# wd-adapter.net
KiCad netlist of a schematic drawn in EAGLE
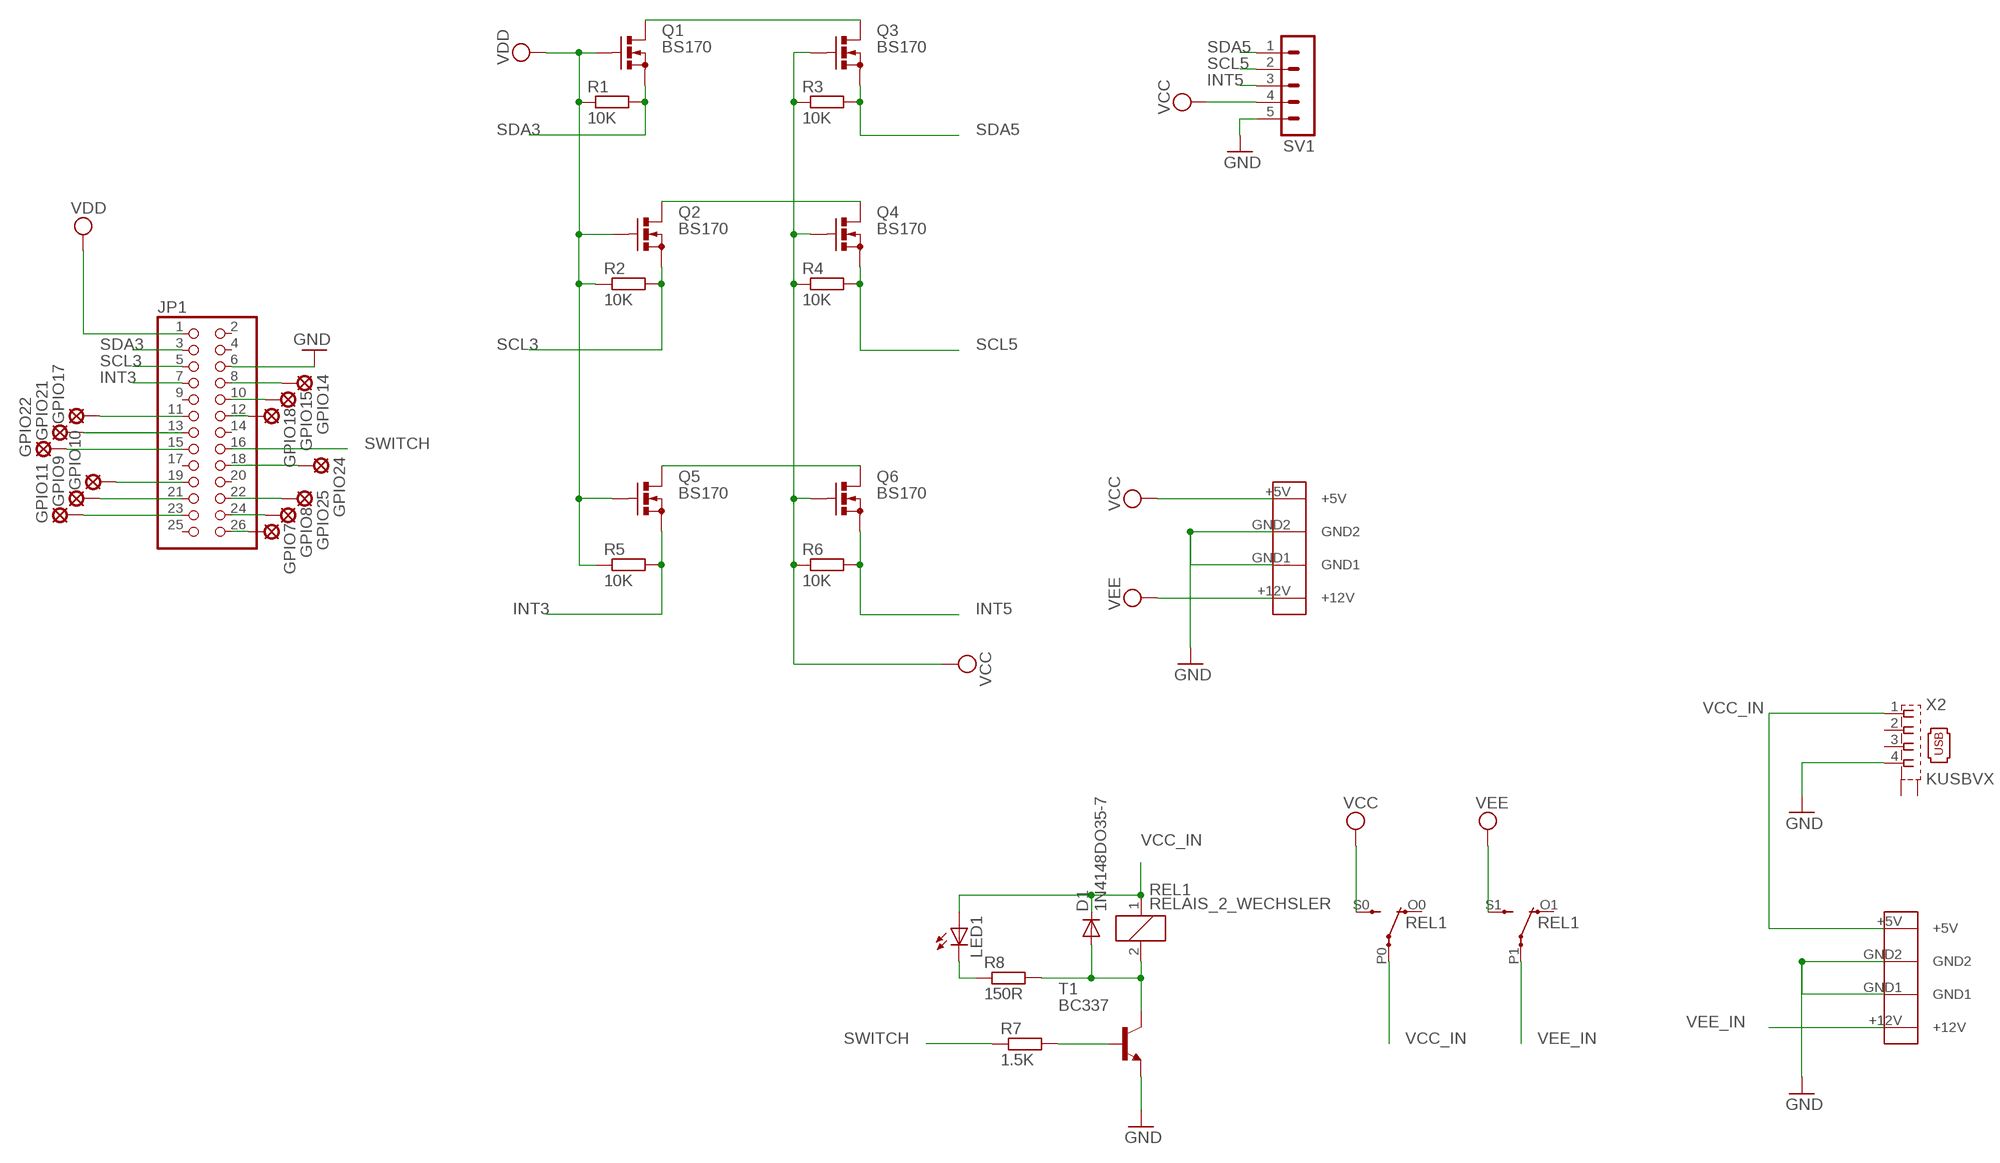
[diagram p0: schematic, sheet 1]

(export (version "E")
  (design (tool "Eeschema 10.0.6"))
  (components
    (comp (ref "D1")
      (value "1N4148DO35-7")
      (footprint "eagle-import:DO35-7")
      (libsource (lib "eagle-import") (part "1N4148DO35-7"))
    )
    (comp (ref "GPIO7")
      (value "LSP10")
      (footprint "eagle-import:LSP10")
      (libsource (lib "eagle-import") (part "LSP10"))
    )
    (comp (ref "GPIO8")
      (value "LSP10")
      (footprint "eagle-import:LSP10")
      (libsource (lib "eagle-import") (part "LSP10"))
    )
    (comp (ref "GPIO9")
      (value "LSP10")
      (footprint "eagle-import:LSP10")
      (libsource (lib "eagle-import") (part "LSP10"))
    )
    (comp (ref "GPIO10")
      (value "LSP10")
      (footprint "eagle-import:LSP10")
      (libsource (lib "eagle-import") (part "LSP10"))
    )
    (comp (ref "GPIO11")
      (value "LSP10")
      (footprint "eagle-import:LSP10")
      (libsource (lib "eagle-import") (part "LSP10"))
    )
    (comp (ref "GPIO14")
      (value "LSP10")
      (footprint "eagle-import:LSP10")
      (libsource (lib "eagle-import") (part "LSP10"))
    )
    (comp (ref "GPIO15")
      (value "LSP10")
      (footprint "eagle-import:LSP10")
      (libsource (lib "eagle-import") (part "LSP10"))
    )
    (comp (ref "GPIO17")
      (value "GPIO17")
      (footprint "eagle-import:LSP10")
      (libsource (lib "eagle-import") (part "LSP10"))
    )
    (comp (ref "GPIO18")
      (value "LSP10")
      (footprint "eagle-import:LSP10")
      (libsource (lib "eagle-import") (part "LSP10"))
    )
    (comp (ref "GPIO21")
      (value "LSP10")
      (footprint "eagle-import:LSP10")
      (libsource (lib "eagle-import") (part "LSP10"))
    )
    (comp (ref "GPIO22")
      (value "LSP10")
      (footprint "eagle-import:LSP10")
      (libsource (lib "eagle-import") (part "LSP10"))
    )
    (comp (ref "GPIO24")
      (value "LSP10")
      (footprint "eagle-import:LSP10")
      (libsource (lib "eagle-import") (part "LSP10"))
    )
    (comp (ref "GPIO25")
      (value "LSP10")
      (footprint "eagle-import:LSP10")
      (libsource (lib "eagle-import") (part "LSP10"))
    )
    (comp (ref "JP1")
      (value "PINHD-2X13")
      (footprint "eagle-import:2X13")
      (libsource (lib "eagle-import") (part "PINHD-2X13"))
    )
    (comp (ref "LED1")
      (value "LED3MM")
      (footprint "eagle-import:LED3MM")
      (libsource (lib "eagle-import") (part "LED3MM"))
    )
    (comp (ref "Q1")
      (value "BS170")
      (footprint "eagle-import:SOT54E")
      (libsource (lib "eagle-import") (part "BS170"))
    )
    (comp (ref "Q2")
      (value "BS170")
      (footprint "eagle-import:SOT54E")
      (libsource (lib "eagle-import") (part "BS170"))
    )
    (comp (ref "Q3")
      (value "BS170")
      (footprint "eagle-import:SOT54E")
      (libsource (lib "eagle-import") (part "BS170"))
    )
    (comp (ref "Q4")
      (value "BS170")
      (footprint "eagle-import:SOT54E")
      (libsource (lib "eagle-import") (part "BS170"))
    )
    (comp (ref "Q5")
      (value "BS170")
      (footprint "eagle-import:SOT54E")
      (libsource (lib "eagle-import") (part "BS170"))
    )
    (comp (ref "Q6")
      (value "BS170")
      (footprint "eagle-import:SOT54E")
      (libsource (lib "eagle-import") (part "BS170"))
    )
    (comp (ref "R1")
      (value "10K")
      (footprint "eagle-import:0207_2V")
      (libsource (lib "eagle-import") (part "R-EU_0207/2V"))
    )
    (comp (ref "R2")
      (value "10K")
      (footprint "eagle-import:0207_2V")
      (libsource (lib "eagle-import") (part "R-EU_0207/2V"))
    )
    (comp (ref "R3")
      (value "10K")
      (footprint "eagle-import:0207_2V")
      (libsource (lib "eagle-import") (part "R-EU_0207/2V"))
    )
    (comp (ref "R4")
      (value "10K")
      (footprint "eagle-import:0207_2V")
      (libsource (lib "eagle-import") (part "R-EU_0207/2V"))
    )
    (comp (ref "R5")
      (value "10K")
      (footprint "eagle-import:0207_2V")
      (libsource (lib "eagle-import") (part "R-EU_0207/2V"))
    )
    (comp (ref "R6")
      (value "10K")
      (footprint "eagle-import:0207_2V")
      (libsource (lib "eagle-import") (part "R-EU_0207/2V"))
    )
    (comp (ref "R7")
      (value "1.5K")
      (footprint "eagle-import:0207_7")
      (libsource (lib "eagle-import") (part "R-EU_0207/7"))
    )
    (comp (ref "R8")
      (value "150R")
      (footprint "eagle-import:0207_2V")
      (libsource (lib "eagle-import") (part "R-EU_0207/2V"))
    )
    (comp (ref "REL1")
      (value "RELAIS_2_WECHSLER")
      (footprint "eagle-import:RELAIS_DIL_M4")
      (libsource (lib "eagle-import") (part "RELAIS_2_WECHSLER"))
    )
    (comp (ref "SV1")
      (value "MA05-1")
      (footprint "eagle-import:MA05-1")
      (libsource (lib "eagle-import") (part "MA05-1"))
    )
    (comp (ref "T1")
      (value "BC337")
      (footprint "eagle-import:TO92")
      (libsource (lib "eagle-import") (part "BC337"))
    )
    (comp (ref "U$1")
      (value "PSW_5")
      (footprint "eagle-import:PSW_5")
      (libsource (lib "eagle-import") (part "PSW_5"))
    )
    (comp (ref "U$3")
      (value "PSW_5")
      (footprint "eagle-import:PSW_5")
      (libsource (lib "eagle-import") (part "PSW_5"))
    )
    (comp (ref "X2")
      (value "KUSBVX")
      (footprint "eagle-import:KUSBVX")
      (libsource (lib "eagle-import") (part "KUSBVX"))
    )
  )
  (nets
    (net (code "1") (name "/INT3") (class "Default")
      (node (ref "JP1") (pin "7") (pinfunction "7_7") (pintype "passive"))
      (node (ref "Q5") (pin "S") (pinfunction "S_S") (pintype "passive"))
      (node (ref "R5") (pin "2") (pinfunction "2_2") (pintype "passive"))
    )
    (net (code "2") (name "/INT5") (class "Default")
      (node (ref "Q6") (pin "S") (pinfunction "S_S") (pintype "passive"))
      (node (ref "R6") (pin "2") (pinfunction "2_2") (pintype "passive"))
      (node (ref "SV1") (pin "3") (pinfunction "3_3") (pintype "passive"))
    )
    (net (code "3") (name "/SCL3") (class "Default")
      (node (ref "JP1") (pin "5") (pinfunction "5_5") (pintype "passive"))
      (node (ref "Q2") (pin "S") (pinfunction "S_S") (pintype "passive"))
      (node (ref "R2") (pin "2") (pinfunction "2_2") (pintype "passive"))
    )
    (net (code "4") (name "/SCL5") (class "Default")
      (node (ref "Q4") (pin "S") (pinfunction "S_S") (pintype "passive"))
      (node (ref "R4") (pin "2") (pinfunction "2_2") (pintype "passive"))
      (node (ref "SV1") (pin "2") (pinfunction "2_2") (pintype "passive"))
    )
    (net (code "5") (name "/SDA3") (class "Default")
      (node (ref "JP1") (pin "3") (pinfunction "3_3") (pintype "passive"))
      (node (ref "Q1") (pin "S") (pinfunction "S_S") (pintype "passive"))
      (node (ref "R1") (pin "2") (pinfunction "2_2") (pintype "passive"))
    )
    (net (code "6") (name "/SDA5") (class "Default")
      (node (ref "Q3") (pin "S") (pinfunction "S_S") (pintype "passive"))
      (node (ref "R3") (pin "2") (pinfunction "2_2") (pintype "passive"))
      (node (ref "SV1") (pin "1") (pinfunction "1_1") (pintype "passive"))
    )
    (net (code "7") (name "/SWITCH") (class "Default")
      (node (ref "JP1") (pin "16") (pinfunction "16_16") (pintype "passive"))
      (node (ref "R7") (pin "1") (pinfunction "1_1") (pintype "passive"))
    )
    (net (code "8") (name "/VCC_IN") (class "Default")
      (node (ref "D1") (pin "C") (pinfunction "C_C") (pintype "passive"))
      (node (ref "LED1") (pin "A") (pinfunction "A_A") (pintype "passive"))
      (node (ref "REL1") (pin "1") (pinfunction "1_1") (pintype "passive"))
      (node (ref "REL1") (pin "P0") (pinfunction "P_P0") (pintype "passive"))
      (node (ref "U$3") (pin "+5V") (pinfunction "+5V_+5V") (pintype "bidirectional"))
      (node (ref "X2") (pin "1") (pinfunction "1_1") (pintype "passive"))
    )
    (net (code "9") (name "/VEE_IN") (class "Default")
      (node (ref "REL1") (pin "P1") (pinfunction "P_P1") (pintype "passive"))
      (node (ref "U$3") (pin "+12V") (pinfunction "+12V_+12V") (pintype "bidirectional"))
    )
    (net (code "10") (name "GND") (class "Default")
      (node (ref "JP1") (pin "6") (pinfunction "6_6") (pintype "passive"))
      (node (ref "SV1") (pin "5") (pinfunction "5_5") (pintype "passive"))
      (node (ref "T1") (pin "1") (pinfunction "E_1") (pintype "passive"))
      (node (ref "U$1") (pin "GND1") (pinfunction "GND1_GND1") (pintype "bidirectional"))
      (node (ref "U$1") (pin "GND2") (pinfunction "GND2_GND2") (pintype "bidirectional"))
      (node (ref "U$3") (pin "GND1") (pinfunction "GND1_GND1") (pintype "bidirectional"))
      (node (ref "U$3") (pin "GND2") (pinfunction "GND2_GND2") (pintype "bidirectional"))
      (node (ref "X2") (pin "4") (pinfunction "4_4") (pintype "passive"))
    )
    (net (code "11") (name "Net-(GPIO7-PadMP)") (class "Default")
      (node (ref "GPIO7") (pin "MP") (pinfunction "MP_MP") (pintype "passive"))
      (node (ref "JP1") (pin "26") (pinfunction "26_26") (pintype "passive"))
    )
    (net (code "12") (name "Net-(GPIO8-PadMP)") (class "Default")
      (node (ref "GPIO8") (pin "MP") (pinfunction "MP_MP") (pintype "passive"))
      (node (ref "JP1") (pin "24") (pinfunction "24_24") (pintype "passive"))
    )
    (net (code "13") (name "Net-(GPIO9-PadMP)") (class "Default")
      (node (ref "GPIO9") (pin "MP") (pinfunction "MP_MP") (pintype "passive"))
      (node (ref "JP1") (pin "21") (pinfunction "21_21") (pintype "passive"))
    )
    (net (code "14") (name "Net-(GPIO10-PadMP)") (class "Default")
      (node (ref "GPIO10") (pin "MP") (pinfunction "MP_MP") (pintype "passive"))
      (node (ref "JP1") (pin "19") (pinfunction "19_19") (pintype "passive"))
    )
    (net (code "15") (name "Net-(GPIO11-PadMP)") (class "Default")
      (node (ref "GPIO11") (pin "MP") (pinfunction "MP_MP") (pintype "passive"))
      (node (ref "JP1") (pin "23") (pinfunction "23_23") (pintype "passive"))
    )
    (net (code "16") (name "Net-(GPIO14-PadMP)") (class "Default")
      (node (ref "GPIO14") (pin "MP") (pinfunction "MP_MP") (pintype "passive"))
      (node (ref "JP1") (pin "8") (pinfunction "8_8") (pintype "passive"))
    )
    (net (code "17") (name "Net-(GPIO15-PadMP)") (class "Default")
      (node (ref "GPIO15") (pin "MP") (pinfunction "MP_MP") (pintype "passive"))
      (node (ref "JP1") (pin "10") (pinfunction "10_10") (pintype "passive"))
    )
    (net (code "18") (name "Net-(GPIO17-PadMP)") (class "Default")
      (node (ref "GPIO17") (pin "MP") (pinfunction "MP_MP") (pintype "passive"))
      (node (ref "JP1") (pin "11") (pinfunction "11_11") (pintype "passive"))
    )
    (net (code "19") (name "Net-(GPIO18-PadMP)") (class "Default")
      (node (ref "GPIO18") (pin "MP") (pinfunction "MP_MP") (pintype "passive"))
      (node (ref "JP1") (pin "12") (pinfunction "12_12") (pintype "passive"))
    )
    (net (code "20") (name "Net-(GPIO21-PadMP)") (class "Default")
      (node (ref "GPIO21") (pin "MP") (pinfunction "MP_MP") (pintype "passive"))
      (node (ref "JP1") (pin "13") (pinfunction "13_13") (pintype "passive"))
    )
    (net (code "21") (name "Net-(GPIO22-PadMP)") (class "Default")
      (node (ref "GPIO22") (pin "MP") (pinfunction "MP_MP") (pintype "passive"))
      (node (ref "JP1") (pin "15") (pinfunction "15_15") (pintype "passive"))
    )
    (net (code "22") (name "Net-(GPIO24-PadMP)") (class "Default")
      (node (ref "GPIO24") (pin "MP") (pinfunction "MP_MP") (pintype "passive"))
      (node (ref "JP1") (pin "18") (pinfunction "18_18") (pintype "passive"))
    )
    (net (code "23") (name "Net-(GPIO25-PadMP)") (class "Default")
      (node (ref "GPIO25") (pin "MP") (pinfunction "MP_MP") (pintype "passive"))
      (node (ref "JP1") (pin "22") (pinfunction "22_22") (pintype "passive"))
    )
    (net (code "24") (name "Net-(LED1-C)") (class "Default")
      (node (ref "LED1") (pin "K") (pinfunction "C_K") (pintype "passive"))
      (node (ref "R8") (pin "1") (pinfunction "1_1") (pintype "passive"))
    )
    (net (code "25") (name "Net-(Q1-PadD)") (class "Default")
      (node (ref "Q1") (pin "D") (pinfunction "D_D") (pintype "passive"))
      (node (ref "Q3") (pin "D") (pinfunction "D_D") (pintype "passive"))
    )
    (net (code "26") (name "Net-(Q2-PadD)") (class "Default")
      (node (ref "Q2") (pin "D") (pinfunction "D_D") (pintype "passive"))
      (node (ref "Q4") (pin "D") (pinfunction "D_D") (pintype "passive"))
    )
    (net (code "27") (name "Net-(Q5-PadD)") (class "Default")
      (node (ref "Q5") (pin "D") (pinfunction "D_D") (pintype "passive"))
      (node (ref "Q6") (pin "D") (pinfunction "D_D") (pintype "passive"))
    )
    (net (code "28") (name "Net-(T1-B)") (class "Default")
      (node (ref "R7") (pin "2") (pinfunction "2_2") (pintype "passive"))
      (node (ref "T1") (pin "2") (pinfunction "B_2") (pintype "passive"))
    )
    (net (code "29") (name "Net-(T1-C)") (class "Default")
      (node (ref "D1") (pin "A") (pinfunction "A_A") (pintype "passive"))
      (node (ref "R8") (pin "2") (pinfunction "2_2") (pintype "passive"))
      (node (ref "REL1") (pin "2") (pinfunction "2_2") (pintype "passive"))
      (node (ref "T1") (pin "3") (pinfunction "C_3") (pintype "passive"))
    )
    (net (code "30") (name "VCC") (class "Default")
      (node (ref "Q3") (pin "G") (pinfunction "G_G") (pintype "passive"))
      (node (ref "Q4") (pin "G") (pinfunction "G_G") (pintype "passive"))
      (node (ref "Q6") (pin "G") (pinfunction "G_G") (pintype "passive"))
      (node (ref "R3") (pin "1") (pinfunction "1_1") (pintype "passive"))
      (node (ref "R4") (pin "1") (pinfunction "1_1") (pintype "passive"))
      (node (ref "R6") (pin "1") (pinfunction "1_1") (pintype "passive"))
      (node (ref "REL1") (pin "S0") (pinfunction "S_S0") (pintype "passive"))
      (node (ref "SV1") (pin "4") (pinfunction "4_4") (pintype "passive"))
      (node (ref "U$1") (pin "+5V") (pinfunction "+5V_+5V") (pintype "bidirectional"))
    )
    (net (code "31") (name "VDD") (class "Default")
      (node (ref "JP1") (pin "1") (pinfunction "1_1") (pintype "passive"))
      (node (ref "Q1") (pin "G") (pinfunction "G_G") (pintype "passive"))
      (node (ref "Q2") (pin "G") (pinfunction "G_G") (pintype "passive"))
      (node (ref "Q5") (pin "G") (pinfunction "G_G") (pintype "passive"))
      (node (ref "R1") (pin "1") (pinfunction "1_1") (pintype "passive"))
      (node (ref "R2") (pin "1") (pinfunction "1_1") (pintype "passive"))
      (node (ref "R5") (pin "1") (pinfunction "1_1") (pintype "passive"))
    )
    (net (code "32") (name "VEE") (class "Default")
      (node (ref "REL1") (pin "S1") (pinfunction "S_S1") (pintype "passive"))
      (node (ref "U$1") (pin "+12V") (pinfunction "+12V_+12V") (pintype "bidirectional"))
    )
    (net (code "33") (name "unconnected-(JP1-Pad2)") (class "Default")
      (node (ref "JP1") (pin "2") (pinfunction "2_2") (pintype "passive"))
    )
    (net (code "34") (name "unconnected-(JP1-Pad4)") (class "Default")
      (node (ref "JP1") (pin "4") (pinfunction "4_4") (pintype "passive"))
    )
    (net (code "35") (name "unconnected-(JP1-Pad9)") (class "Default")
      (node (ref "JP1") (pin "9") (pinfunction "9_9") (pintype "passive"))
    )
    (net (code "36") (name "unconnected-(JP1-Pad14)") (class "Default")
      (node (ref "JP1") (pin "14") (pinfunction "14_14") (pintype "passive"))
    )
    (net (code "37") (name "unconnected-(JP1-Pad17)") (class "Default")
      (node (ref "JP1") (pin "17") (pinfunction "17_17") (pintype "passive"))
    )
    (net (code "38") (name "unconnected-(JP1-Pad20)") (class "Default")
      (node (ref "JP1") (pin "20") (pinfunction "20_20") (pintype "passive"))
    )
    (net (code "39") (name "unconnected-(JP1-Pad25)") (class "Default")
      (node (ref "JP1") (pin "25") (pinfunction "25_25") (pintype "passive"))
    )
    (net (code "40") (name "unconnected-(REL1B-O-PadO0)") (class "Default")
      (node (ref "REL1") (pin "O0") (pinfunction "O_O0") (pintype "passive"))
    )
    (net (code "41") (name "unconnected-(REL1C-O-PadO1)") (class "Default")
      (node (ref "REL1") (pin "O1") (pinfunction "O_O1") (pintype "passive"))
    )
    (net (code "42") (name "unconnected-(X2-Pad2)") (class "Default")
      (node (ref "X2") (pin "2") (pinfunction "2_2") (pintype "passive"))
    )
    (net (code "43") (name "unconnected-(X2-Pad3)") (class "Default")
      (node (ref "X2") (pin "3") (pinfunction "3_3") (pintype "passive"))
    )
    (net (code "44") (name "unconnected-(X2-S1-PadM1)") (class "Default")
      (node (ref "X2") (pin "M1") (pinfunction "S1_M1") (pintype "passive"))
    )
    (net (code "45") (name "unconnected-(X2-S2-PadM2)") (class "Default")
      (node (ref "X2") (pin "M2") (pinfunction "S2_M2") (pintype "passive"))
    )
  )
)
